# RelayWingTester.net
KiCad netlist of a schematic drawn in EAGLE
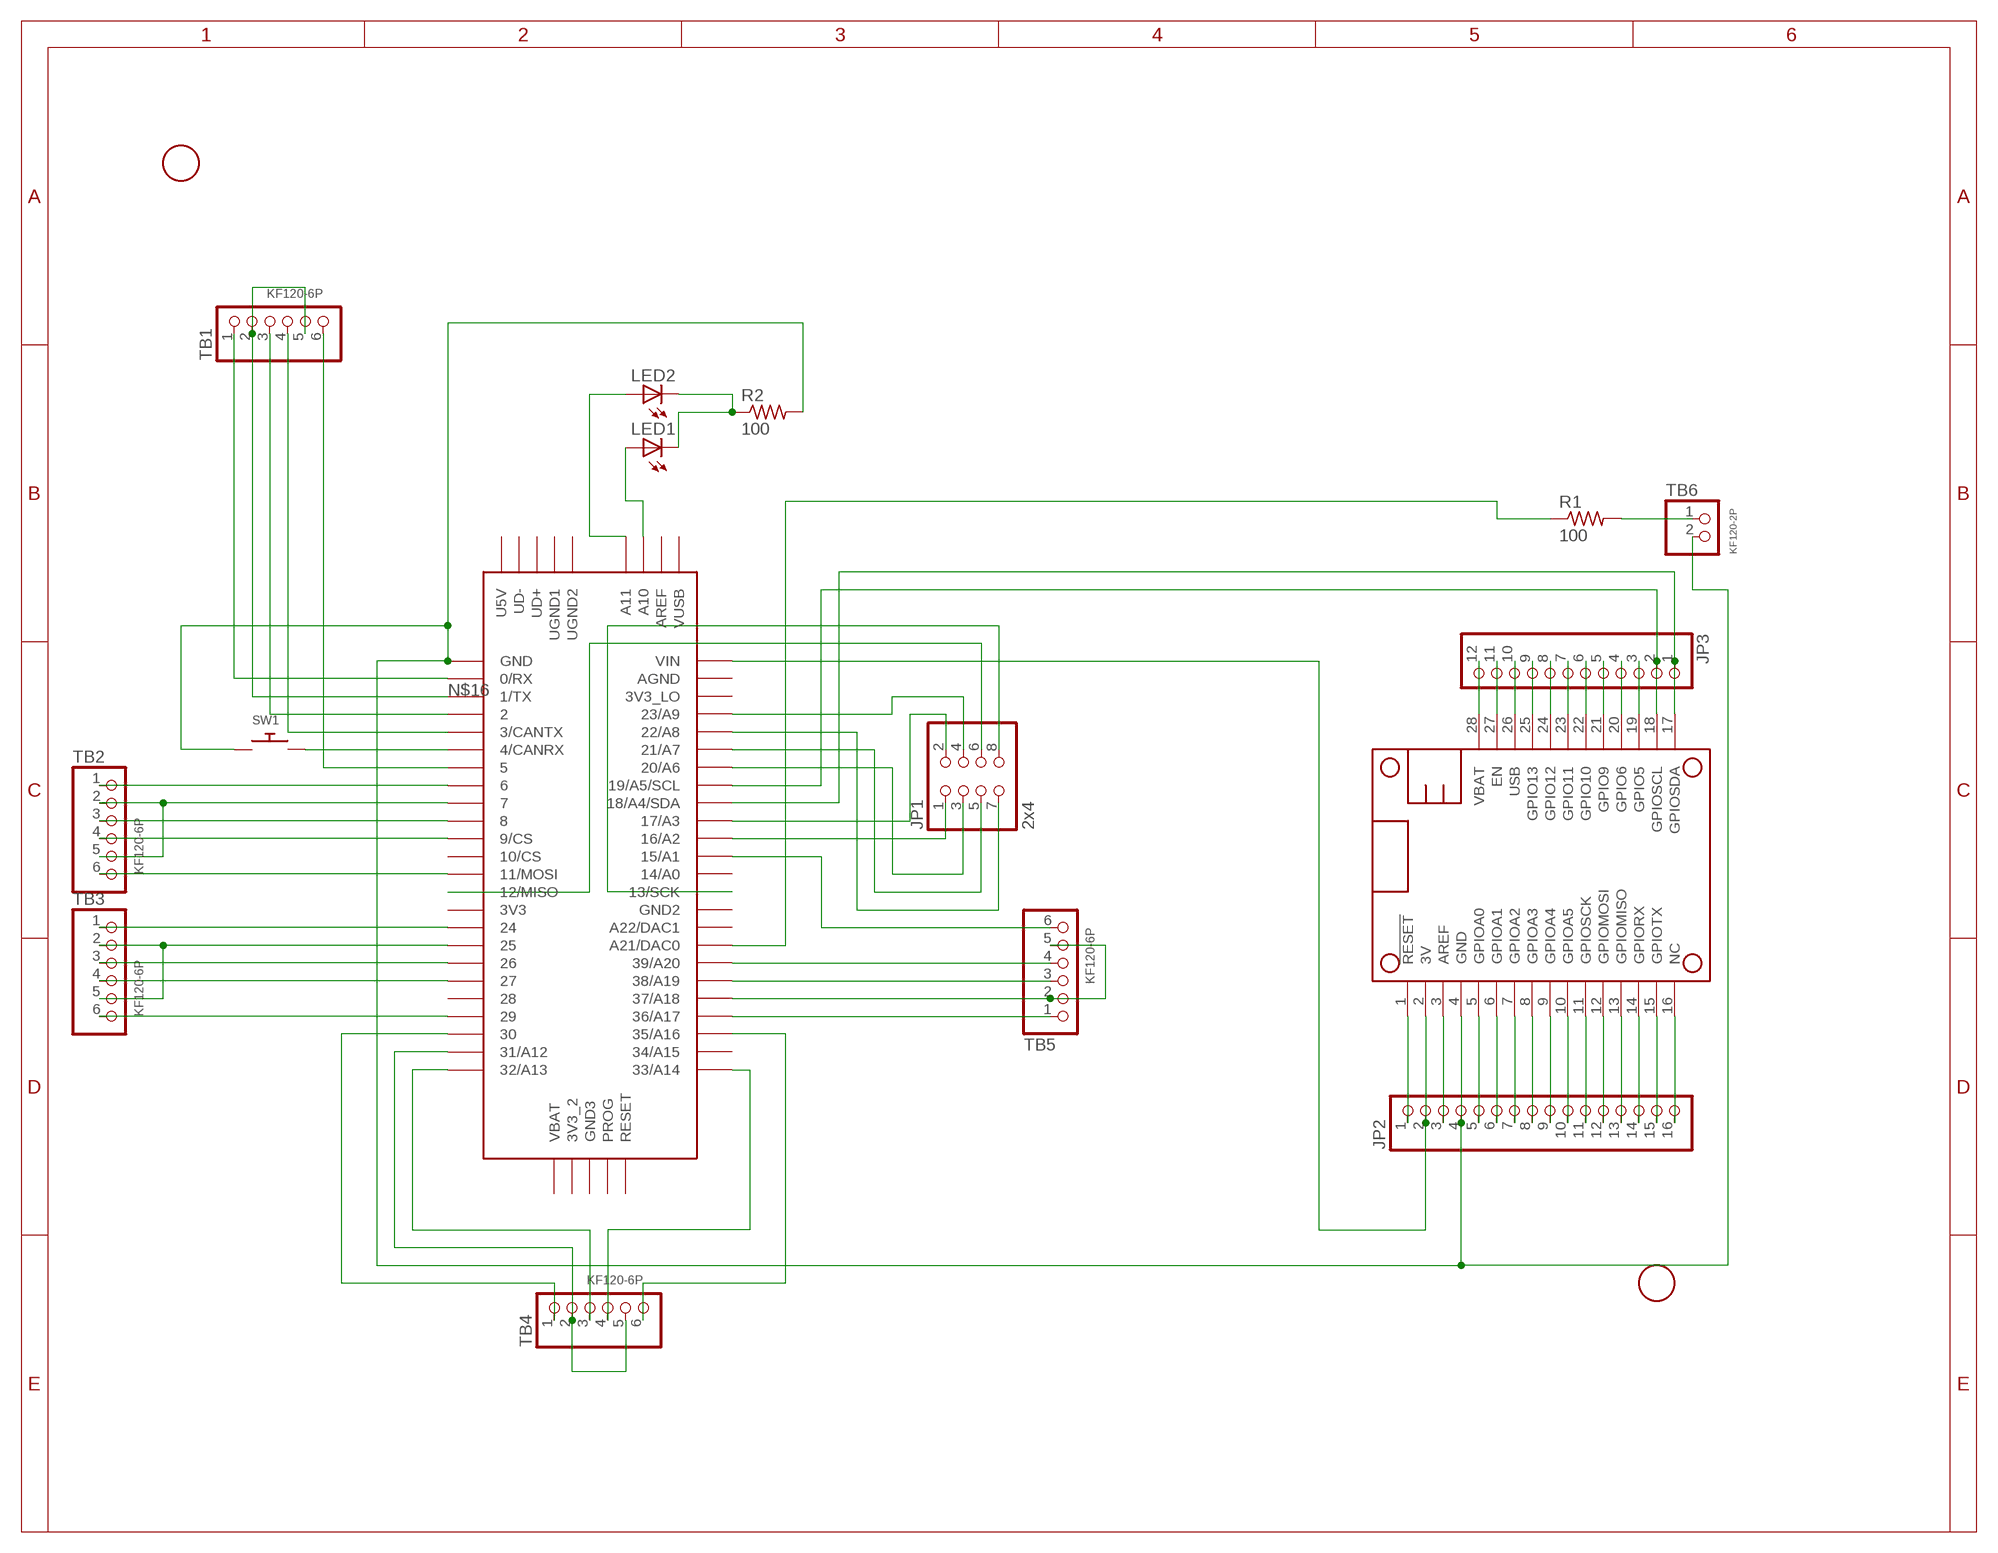
[diagram p0: schematic, sheet 1]

(export (version "E")
  (design (tool "Eeschema 10.0.6"))
  (components
    (comp (ref "JP1")
      (value "2x4")
      (footprint "eagle-import:2X04")
      (libsource (lib "eagle-import") (part "PINHD-2X4"))
    )
    (comp (ref "JP2")
      (value "PINHD-1X16")
      (footprint "eagle-import:1X16")
      (libsource (lib "eagle-import") (part "PINHD-1X16"))
    )
    (comp (ref "JP3")
      (value "PINHD-1X12")
      (footprint "eagle-import:1X12")
      (libsource (lib "eagle-import") (part "PINHD-1X12"))
    )
    (comp (ref "LED1")
      (value "LED5MM")
      (footprint "eagle-import:LED5MM")
      (libsource (lib "eagle-import") (part "LED5MM"))
    )
    (comp (ref "LED2")
      (value "LED5MM")
      (footprint "eagle-import:LED5MM")
      (libsource (lib "eagle-import") (part "LED5MM"))
    )
    (comp (ref "MS1")
      (value "FEATHERWING_NODIM")
      (footprint "eagle-import:FEATHERWING_DIM")
      (libsource (lib "eagle-import") (part "FEATHERWING_NODIM"))
    )
    (comp (ref "R1")
      (value "100")
      (footprint "eagle-import:0207_10")
      (libsource (lib "eagle-import") (part "resistor_348_R-US_0207/10"))
    )
    (comp (ref "R2")
      (value "100")
      (footprint "eagle-import:0207_10")
      (libsource (lib "eagle-import") (part "R-US_0207/10"))
    )
    (comp (ref "SW1")
      (value "SWITCH_PUSHBUTTONSOFTTOUCHSMD_SJ")
      (footprint "eagle-import:PUSHBUTTON_SMD_SJ")
      (libsource (lib "eagle-import") (part "SWITCH_PUSHBUTTONSOFTTOUCHSMD_SJ"))
    )
    (comp (ref "TB1")
      (value "KF120-6P")
      (footprint "eagle-import:KF120-6P_ROUND")
      (libsource (lib "eagle-import") (part "KF120-6P"))
    )
    (comp (ref "TB2")
      (value "KF120-6P")
      (footprint "eagle-import:KF120-6P_ROUND")
      (libsource (lib "eagle-import") (part "KF120-6P"))
    )
    (comp (ref "TB3")
      (value "KF120-6P")
      (footprint "eagle-import:KF120-6P_ROUND")
      (libsource (lib "eagle-import") (part "KF120-6P"))
    )
    (comp (ref "TB4")
      (value "KF120-6P")
      (footprint "eagle-import:KF120-6P_ROUND")
      (libsource (lib "eagle-import") (part "KF120-6P"))
    )
    (comp (ref "TB5")
      (value "KF120-6P")
      (footprint "eagle-import:KF120-6P_ROUND")
      (libsource (lib "eagle-import") (part "KF120-6P"))
    )
    (comp (ref "TB6")
      (value "KF120-2P")
      (footprint "eagle-import:KF120-2P_ROUND")
      (libsource (lib "eagle-import") (part "KF120-2P"))
    )
    (comp (ref "U$2")
      (value "FIDUCIAL")
      (footprint "eagle-import:FIDUCIAL_1MM")
      (libsource (lib "eagle-import") (part "FIDUCIAL"))
    )
    (comp (ref "U$3")
      (value "FIDUCIAL")
      (footprint "eagle-import:FIDUCIAL_1MM")
      (libsource (lib "eagle-import") (part "FIDUCIAL"))
    )
    (comp (ref "U$4")
      (value "TEENSY_3.5/3.6")
      (footprint "eagle-import:TEENSY_3.5_3.6")
      (libsource (lib "eagle-import") (part "TEENSY_3.5/3.6"))
    )
  )
  (nets
    (net (code "1") (name "/N$16") (class "Default")
      (node (ref "TB1") (pin "1") (pinfunction "1_1") (pintype "passive"))
      (node (ref "U$4") (pin "0/RX") (pinfunction "0/RX_0/RX") (pintype "bidirectional"))
    )
    (net (code "2") (name "Net-(JP1-Pad1)") (class "Default")
      (node (ref "JP1") (pin "1") (pinfunction "1_1") (pintype "passive"))
      (node (ref "U$4") (pin "16/A2") (pinfunction "16/A2_16/A2") (pintype "bidirectional"))
    )
    (net (code "3") (name "Net-(JP1-Pad2)") (class "Default")
      (node (ref "JP1") (pin "2") (pinfunction "2_2") (pintype "passive"))
      (node (ref "U$4") (pin "17/A3") (pinfunction "17/A3_17/A3") (pintype "bidirectional"))
    )
    (net (code "4") (name "Net-(JP1-Pad3)") (class "Default")
      (node (ref "JP1") (pin "3") (pinfunction "3_3") (pintype "passive"))
      (node (ref "U$4") (pin "20/A6") (pinfunction "20/A6_20/A6") (pintype "bidirectional"))
    )
    (net (code "5") (name "Net-(JP1-Pad4)") (class "Default")
      (node (ref "JP1") (pin "4") (pinfunction "4_4") (pintype "passive"))
      (node (ref "U$4") (pin "23/A9") (pinfunction "23/A9_23/A9") (pintype "bidirectional"))
    )
    (net (code "6") (name "Net-(JP1-Pad5)") (class "Default")
      (node (ref "JP1") (pin "5") (pinfunction "5_5") (pintype "passive"))
      (node (ref "U$4") (pin "21/A7") (pinfunction "21/A7_21/A7") (pintype "bidirectional"))
    )
    (net (code "7") (name "Net-(JP1-Pad6)") (class "Default")
      (node (ref "JP1") (pin "6") (pinfunction "6_6") (pintype "passive"))
      (node (ref "U$4") (pin "12/MISO") (pinfunction "12/MISO_12/MISO") (pintype "bidirectional"))
    )
    (net (code "8") (name "Net-(JP1-Pad7)") (class "Default")
      (node (ref "JP1") (pin "7") (pinfunction "7_7") (pintype "passive"))
      (node (ref "U$4") (pin "22/A8") (pinfunction "22/A8_22/A8") (pintype "bidirectional"))
    )
    (net (code "9") (name "Net-(JP1-Pad8)") (class "Default")
      (node (ref "JP1") (pin "8") (pinfunction "8_8") (pintype "passive"))
      (node (ref "U$4") (pin "13/SCK") (pinfunction "13/SCK_13/SCK") (pintype "bidirectional"))
    )
    (net (code "10") (name "Net-(LED1-C)") (class "Default")
      (node (ref "LED1") (pin "K") (pinfunction "C_K") (pintype "passive"))
      (node (ref "LED2") (pin "K") (pinfunction "C_K") (pintype "passive"))
      (node (ref "R2") (pin "1") (pinfunction "1_1") (pintype "passive"))
    )
    (net (code "11") (name "Net-(LED1-PadA)") (class "Default")
      (node (ref "LED1") (pin "A") (pinfunction "A_A") (pintype "passive"))
      (node (ref "U$4") (pin "A10") (pinfunction "A10_A10") (pintype "bidirectional"))
    )
    (net (code "12") (name "Net-(LED2-PadA)") (class "Default")
      (node (ref "LED2") (pin "A") (pinfunction "A_A") (pintype "passive"))
      (node (ref "U$4") (pin "A11") (pinfunction "A11_A11") (pintype "bidirectional"))
    )
    (net (code "13") (name "Net-(MS1-3V)") (class "Default")
      (node (ref "JP2") (pin "2") (pinfunction "2_2") (pintype "passive"))
      (node (ref "MS1") (pin "2") (pinfunction "3V_2") (pintype "power_in"))
      (node (ref "U$4") (pin "VIN") (pinfunction "VIN_VIN") (pintype "bidirectional"))
    )
    (net (code "14") (name "Net-(MS1-AREF)") (class "Default")
      (node (ref "JP2") (pin "3") (pinfunction "3_3") (pintype "passive"))
      (node (ref "MS1") (pin "3") (pinfunction "AREF_3") (pintype "passive"))
    )
    (net (code "15") (name "Net-(MS1-EN)") (class "Default")
      (node (ref "JP3") (pin "11") (pinfunction "11_11") (pintype "passive"))
      (node (ref "MS1") (pin "27") (pinfunction "EN_27") (pintype "passive"))
    )
    (net (code "16") (name "Net-(MS1-GND)") (class "Default")
      (node (ref "JP2") (pin "4") (pinfunction "4_4") (pintype "passive"))
      (node (ref "MS1") (pin "4") (pinfunction "GND_4") (pintype "power_in"))
      (node (ref "R2") (pin "2") (pinfunction "2_2") (pintype "passive"))
      (node (ref "SW1") (pin "P$1") (pinfunction "P$1_P$1") (pintype "passive"))
      (node (ref "TB6") (pin "2") (pinfunction "2_2") (pintype "passive"))
      (node (ref "U$4") (pin "GND") (pinfunction "GND_GND") (pintype "bidirectional"))
    )
    (net (code "17") (name "Net-(MS1-GPIO5)") (class "Default")
      (node (ref "JP3") (pin "3") (pinfunction "3_3") (pintype "passive"))
      (node (ref "MS1") (pin "19") (pinfunction "GPIO5_19") (pintype "bidirectional"))
    )
    (net (code "18") (name "Net-(MS1-GPIO6)") (class "Default")
      (node (ref "JP3") (pin "4") (pinfunction "4_4") (pintype "passive"))
      (node (ref "MS1") (pin "20") (pinfunction "GPIO6_20") (pintype "bidirectional"))
    )
    (net (code "19") (name "Net-(MS1-GPIO9)") (class "Default")
      (node (ref "JP3") (pin "5") (pinfunction "5_5") (pintype "passive"))
      (node (ref "MS1") (pin "21") (pinfunction "GPIO9_21") (pintype "bidirectional"))
    )
    (net (code "20") (name "Net-(MS1-GPIO10)") (class "Default")
      (node (ref "JP3") (pin "6") (pinfunction "6_6") (pintype "passive"))
      (node (ref "MS1") (pin "22") (pinfunction "GPIO10_22") (pintype "bidirectional"))
    )
    (net (code "21") (name "Net-(MS1-GPIO11)") (class "Default")
      (node (ref "JP3") (pin "7") (pinfunction "7_7") (pintype "passive"))
      (node (ref "MS1") (pin "23") (pinfunction "GPIO11_23") (pintype "bidirectional"))
    )
    (net (code "22") (name "Net-(MS1-GPIO12)") (class "Default")
      (node (ref "JP3") (pin "8") (pinfunction "8_8") (pintype "passive"))
      (node (ref "MS1") (pin "24") (pinfunction "GPIO12_24") (pintype "bidirectional"))
    )
    (net (code "23") (name "Net-(MS1-GPIO13)") (class "Default")
      (node (ref "JP3") (pin "9") (pinfunction "9_9") (pintype "passive"))
      (node (ref "MS1") (pin "25") (pinfunction "GPIO13_25") (pintype "bidirectional"))
    )
    (net (code "24") (name "Net-(MS1-GPIOA0)") (class "Default")
      (node (ref "JP2") (pin "5") (pinfunction "5_5") (pintype "passive"))
      (node (ref "MS1") (pin "5") (pinfunction "GPIOA0_5") (pintype "bidirectional"))
    )
    (net (code "25") (name "Net-(MS1-GPIOA1)") (class "Default")
      (node (ref "JP2") (pin "6") (pinfunction "6_6") (pintype "passive"))
      (node (ref "MS1") (pin "6") (pinfunction "GPIOA1_6") (pintype "bidirectional"))
    )
    (net (code "26") (name "Net-(MS1-GPIOA2)") (class "Default")
      (node (ref "JP2") (pin "7") (pinfunction "7_7") (pintype "passive"))
      (node (ref "MS1") (pin "7") (pinfunction "GPIOA2_7") (pintype "bidirectional"))
    )
    (net (code "27") (name "Net-(MS1-GPIOA3)") (class "Default")
      (node (ref "JP2") (pin "8") (pinfunction "8_8") (pintype "passive"))
      (node (ref "MS1") (pin "8") (pinfunction "GPIOA3_8") (pintype "bidirectional"))
    )
    (net (code "28") (name "Net-(MS1-GPIOA4)") (class "Default")
      (node (ref "JP2") (pin "9") (pinfunction "9_9") (pintype "passive"))
      (node (ref "MS1") (pin "9") (pinfunction "GPIOA4_9") (pintype "bidirectional"))
    )
    (net (code "29") (name "Net-(MS1-GPIOA5)") (class "Default")
      (node (ref "JP2") (pin "10") (pinfunction "10_10") (pintype "passive"))
      (node (ref "MS1") (pin "10") (pinfunction "GPIOA5_10") (pintype "bidirectional"))
    )
    (net (code "30") (name "Net-(MS1-GPIOMISO)") (class "Default")
      (node (ref "JP2") (pin "13") (pinfunction "13_13") (pintype "passive"))
      (node (ref "MS1") (pin "13") (pinfunction "GPIOMISO_13") (pintype "bidirectional"))
    )
    (net (code "31") (name "Net-(MS1-GPIOMOSI)") (class "Default")
      (node (ref "JP2") (pin "12") (pinfunction "12_12") (pintype "passive"))
      (node (ref "MS1") (pin "12") (pinfunction "GPIOMOSI_12") (pintype "bidirectional"))
    )
    (net (code "32") (name "Net-(MS1-GPIORX)") (class "Default")
      (node (ref "JP2") (pin "14") (pinfunction "14_14") (pintype "passive"))
      (node (ref "MS1") (pin "14") (pinfunction "GPIORX_14") (pintype "bidirectional"))
    )
    (net (code "33") (name "Net-(MS1-GPIOSCK)") (class "Default")
      (node (ref "JP2") (pin "11") (pinfunction "11_11") (pintype "passive"))
      (node (ref "MS1") (pin "11") (pinfunction "GPIOSCK_11") (pintype "bidirectional"))
    )
    (net (code "34") (name "Net-(MS1-GPIOSCL)") (class "Default")
      (node (ref "JP3") (pin "2") (pinfunction "2_2") (pintype "passive"))
      (node (ref "MS1") (pin "18") (pinfunction "GPIOSCL_18") (pintype "bidirectional"))
      (node (ref "U$4") (pin "19/A5/SCL") (pinfunction "19/A5/SCL_19/A5/SCL") (pintype "bidirectional"))
    )
    (net (code "35") (name "Net-(MS1-GPIOSDA)") (class "Default")
      (node (ref "JP3") (pin "1") (pinfunction "1_1") (pintype "passive"))
      (node (ref "MS1") (pin "17") (pinfunction "GPIOSDA_17") (pintype "bidirectional"))
      (node (ref "U$4") (pin "18/A4/SDA") (pinfunction "18/A4/SDA_18/A4/SDA") (pintype "bidirectional"))
    )
    (net (code "36") (name "Net-(MS1-GPIOTX)") (class "Default")
      (node (ref "JP2") (pin "15") (pinfunction "15_15") (pintype "passive"))
      (node (ref "MS1") (pin "15") (pinfunction "GPIOTX_15") (pintype "bidirectional"))
    )
    (net (code "37") (name "Net-(MS1-NC)") (class "Default")
      (node (ref "JP2") (pin "16") (pinfunction "16_16") (pintype "passive"))
      (node (ref "MS1") (pin "16") (pinfunction "NC_16") (pintype "passive"))
    )
    (net (code "38") (name "Net-(MS1-USB)") (class "Default")
      (node (ref "JP3") (pin "10") (pinfunction "10_10") (pintype "passive"))
      (node (ref "MS1") (pin "26") (pinfunction "USB_26") (pintype "power_in"))
    )
    (net (code "39") (name "Net-(MS1-VBAT)") (class "Default")
      (node (ref "JP3") (pin "12") (pinfunction "12_12") (pintype "passive"))
      (node (ref "MS1") (pin "28") (pinfunction "VBAT_28") (pintype "power_in"))
    )
    (net (code "40") (name "Net-(MS1-~{RESET})") (class "Default")
      (node (ref "JP2") (pin "1") (pinfunction "1_1") (pintype "passive"))
      (node (ref "MS1") (pin "1") (pinfunction "~{RESET}_1") (pintype "input"))
    )
    (net (code "41") (name "Net-(R1-Pad2)") (class "Default")
      (node (ref "R1") (pin "2") (pinfunction "2_2") (pintype "passive"))
      (node (ref "TB6") (pin "1") (pinfunction "1_1") (pintype "passive"))
    )
    (net (code "42") (name "Net-(SW1-PadP$2)") (class "Default")
      (node (ref "SW1") (pin "P$2") (pinfunction "P$2_P$2") (pintype "passive"))
      (node (ref "U$4") (pin "4/CANRX") (pinfunction "4/CANRX_4/CANRX") (pintype "bidirectional"))
    )
    (net (code "43") (name "Net-(TB1-Pad2)") (class "Default")
      (node (ref "TB1") (pin "2") (pinfunction "2_2") (pintype "passive"))
      (node (ref "TB1") (pin "5") (pinfunction "5_5") (pintype "passive"))
      (node (ref "U$4") (pin "1/TX") (pinfunction "1/TX_1/TX") (pintype "bidirectional"))
    )
    (net (code "44") (name "Net-(TB1-Pad3)") (class "Default")
      (node (ref "TB1") (pin "3") (pinfunction "3_3") (pintype "passive"))
      (node (ref "U$4") (pin "2") (pinfunction "2_2") (pintype "bidirectional"))
    )
    (net (code "45") (name "Net-(TB1-Pad4)") (class "Default")
      (node (ref "TB1") (pin "4") (pinfunction "4_4") (pintype "passive"))
      (node (ref "U$4") (pin "3/CANTX") (pinfunction "3/CANTX_3/CANTX") (pintype "bidirectional"))
    )
    (net (code "46") (name "Net-(TB1-Pad6)") (class "Default")
      (node (ref "TB1") (pin "6") (pinfunction "6_6") (pintype "passive"))
      (node (ref "U$4") (pin "5") (pinfunction "5_5") (pintype "bidirectional"))
    )
    (net (code "47") (name "Net-(TB2-Pad1)") (class "Default")
      (node (ref "TB2") (pin "1") (pinfunction "1_1") (pintype "passive"))
      (node (ref "U$4") (pin "6") (pinfunction "6_6") (pintype "bidirectional"))
    )
    (net (code "48") (name "Net-(TB2-Pad2)") (class "Default")
      (node (ref "TB2") (pin "2") (pinfunction "2_2") (pintype "passive"))
      (node (ref "TB2") (pin "5") (pinfunction "5_5") (pintype "passive"))
      (node (ref "U$4") (pin "7") (pinfunction "7_7") (pintype "bidirectional"))
    )
    (net (code "49") (name "Net-(TB2-Pad3)") (class "Default")
      (node (ref "TB2") (pin "3") (pinfunction "3_3") (pintype "passive"))
      (node (ref "U$4") (pin "8") (pinfunction "8_8") (pintype "bidirectional"))
    )
    (net (code "50") (name "Net-(TB2-Pad4)") (class "Default")
      (node (ref "TB2") (pin "4") (pinfunction "4_4") (pintype "passive"))
      (node (ref "U$4") (pin "9/CS") (pinfunction "9/CS_9/CS") (pintype "bidirectional"))
    )
    (net (code "51") (name "Net-(TB2-Pad6)") (class "Default")
      (node (ref "TB2") (pin "6") (pinfunction "6_6") (pintype "passive"))
      (node (ref "U$4") (pin "11/MOSI") (pinfunction "11/MOSI_11/MOSI") (pintype "bidirectional"))
    )
    (net (code "52") (name "Net-(TB3-Pad1)") (class "Default")
      (node (ref "TB3") (pin "1") (pinfunction "1_1") (pintype "passive"))
      (node (ref "U$4") (pin "24") (pinfunction "24_24") (pintype "bidirectional"))
    )
    (net (code "53") (name "Net-(TB3-Pad2)") (class "Default")
      (node (ref "TB3") (pin "2") (pinfunction "2_2") (pintype "passive"))
      (node (ref "TB3") (pin "5") (pinfunction "5_5") (pintype "passive"))
      (node (ref "U$4") (pin "25") (pinfunction "25_25") (pintype "bidirectional"))
    )
    (net (code "54") (name "Net-(TB3-Pad3)") (class "Default")
      (node (ref "TB3") (pin "3") (pinfunction "3_3") (pintype "passive"))
      (node (ref "U$4") (pin "26") (pinfunction "26_26") (pintype "bidirectional"))
    )
    (net (code "55") (name "Net-(TB3-Pad4)") (class "Default")
      (node (ref "TB3") (pin "4") (pinfunction "4_4") (pintype "passive"))
      (node (ref "U$4") (pin "27") (pinfunction "27_27") (pintype "bidirectional"))
    )
    (net (code "56") (name "Net-(TB3-Pad6)") (class "Default")
      (node (ref "TB3") (pin "6") (pinfunction "6_6") (pintype "passive"))
      (node (ref "U$4") (pin "29") (pinfunction "29_29") (pintype "bidirectional"))
    )
    (net (code "57") (name "Net-(TB4-Pad1)") (class "Default")
      (node (ref "TB4") (pin "1") (pinfunction "1_1") (pintype "passive"))
      (node (ref "U$4") (pin "30") (pinfunction "30_30") (pintype "bidirectional"))
    )
    (net (code "58") (name "Net-(TB4-Pad2)") (class "Default")
      (node (ref "TB4") (pin "2") (pinfunction "2_2") (pintype "passive"))
      (node (ref "TB4") (pin "5") (pinfunction "5_5") (pintype "passive"))
      (node (ref "U$4") (pin "31/A12") (pinfunction "31/A12_31/A12") (pintype "bidirectional"))
    )
    (net (code "59") (name "Net-(TB4-Pad3)") (class "Default")
      (node (ref "TB4") (pin "3") (pinfunction "3_3") (pintype "passive"))
      (node (ref "U$4") (pin "32/A13") (pinfunction "32/A13_32/A13") (pintype "bidirectional"))
    )
    (net (code "60") (name "Net-(TB4-Pad4)") (class "Default")
      (node (ref "TB4") (pin "4") (pinfunction "4_4") (pintype "passive"))
      (node (ref "U$4") (pin "33/A14") (pinfunction "33/A14_33/A14") (pintype "bidirectional"))
    )
    (net (code "61") (name "Net-(TB4-Pad6)") (class "Default")
      (node (ref "TB4") (pin "6") (pinfunction "6_6") (pintype "passive"))
      (node (ref "U$4") (pin "35/A16") (pinfunction "35/A16_35/A16") (pintype "bidirectional"))
    )
    (net (code "62") (name "Net-(TB5-Pad1)") (class "Default")
      (node (ref "TB5") (pin "1") (pinfunction "1_1") (pintype "passive"))
      (node (ref "U$4") (pin "36/A17") (pinfunction "36/A17_36/A17") (pintype "bidirectional"))
    )
    (net (code "63") (name "Net-(TB5-Pad2)") (class "Default")
      (node (ref "TB5") (pin "2") (pinfunction "2_2") (pintype "passive"))
      (node (ref "TB5") (pin "5") (pinfunction "5_5") (pintype "passive"))
      (node (ref "U$4") (pin "37/A18") (pinfunction "37/A18_37/A18") (pintype "bidirectional"))
    )
    (net (code "64") (name "Net-(TB5-Pad3)") (class "Default")
      (node (ref "TB5") (pin "3") (pinfunction "3_3") (pintype "passive"))
      (node (ref "U$4") (pin "38/A19") (pinfunction "38/A19_38/A19") (pintype "bidirectional"))
    )
    (net (code "65") (name "Net-(TB5-Pad4)") (class "Default")
      (node (ref "TB5") (pin "4") (pinfunction "4_4") (pintype "passive"))
      (node (ref "U$4") (pin "39/A20") (pinfunction "39/A20_39/A20") (pintype "bidirectional"))
    )
    (net (code "66") (name "Net-(TB5-Pad6)") (class "Default")
      (node (ref "TB5") (pin "6") (pinfunction "6_6") (pintype "passive"))
      (node (ref "U$4") (pin "15/A1") (pinfunction "15/A1_15/A1") (pintype "bidirectional"))
    )
    (net (code "67") (name "Net-(U$4-A21{slash}DAC0)") (class "Default")
      (node (ref "R1") (pin "1") (pinfunction "1_1") (pintype "passive"))
      (node (ref "U$4") (pin "21/DAC0") (pinfunction "A21/DAC0_21/DAC0") (pintype "bidirectional"))
    )
    (net (code "68") (name "unconnected-(U$4-Pad3V3)") (class "Default")
      (node (ref "U$4") (pin "3V3") (pinfunction "3V3_3V3") (pintype "bidirectional"))
    )
    (net (code "69") (name "unconnected-(U$4-Pad3V3_2)") (class "Default")
      (node (ref "U$4") (pin "3V3_2") (pinfunction "3V3_2_3V3_2") (pintype "bidirectional"))
    )
    (net (code "70") (name "unconnected-(U$4-Pad3V3_LO)") (class "Default")
      (node (ref "U$4") (pin "3V3_LO") (pinfunction "3V3_LO_3V3_LO") (pintype "bidirectional"))
    )
    (net (code "71") (name "unconnected-(U$4-Pad10{slash}CS)") (class "Default")
      (node (ref "U$4") (pin "10/CS") (pinfunction "10/CS_10/CS") (pintype "bidirectional"))
    )
    (net (code "72") (name "unconnected-(U$4-Pad14{slash}A0)") (class "Default")
      (node (ref "U$4") (pin "14/A0") (pinfunction "14/A0_14/A0") (pintype "bidirectional"))
    )
    (net (code "73") (name "unconnected-(U$4-Pad28)") (class "Default")
      (node (ref "U$4") (pin "28") (pinfunction "28_28") (pintype "bidirectional"))
    )
    (net (code "74") (name "unconnected-(U$4-Pad34{slash}A15)") (class "Default")
      (node (ref "U$4") (pin "34/A15") (pinfunction "34/A15_34/A15") (pintype "bidirectional"))
    )
    (net (code "75") (name "unconnected-(U$4-PadA22{slash}DAC1)") (class "Default")
      (node (ref "U$4") (pin "A22/DAC1") (pinfunction "A22/DAC1_A22/DAC1") (pintype "bidirectional"))
    )
    (net (code "76") (name "unconnected-(U$4-PadAGND)") (class "Default")
      (node (ref "U$4") (pin "AGND") (pinfunction "AGND_AGND") (pintype "bidirectional"))
    )
    (net (code "77") (name "unconnected-(U$4-PadAREF)") (class "Default")
      (node (ref "U$4") (pin "AREF") (pinfunction "AREF_AREF") (pintype "bidirectional"))
    )
    (net (code "78") (name "unconnected-(U$4-PadGND2)") (class "Default")
      (node (ref "U$4") (pin "GND2") (pinfunction "GND2_GND2") (pintype "bidirectional"))
    )
    (net (code "79") (name "unconnected-(U$4-PadGND3)") (class "Default")
      (node (ref "U$4") (pin "GND3") (pinfunction "GND3_GND3") (pintype "bidirectional"))
    )
    (net (code "80") (name "unconnected-(U$4-PadPROG)") (class "Default")
      (node (ref "U$4") (pin "PROG") (pinfunction "PROG_PROG") (pintype "bidirectional"))
    )
    (net (code "81") (name "unconnected-(U$4-PadRESET)") (class "Default")
      (node (ref "U$4") (pin "RESET") (pinfunction "RESET_RESET") (pintype "bidirectional"))
    )
    (net (code "82") (name "unconnected-(U$4-PadU5V)") (class "Default")
      (node (ref "U$4") (pin "U5V") (pinfunction "U5V_U5V") (pintype "bidirectional"))
    )
    (net (code "83") (name "unconnected-(U$4-PadUD+)") (class "Default")
      (node (ref "U$4") (pin "UD+") (pinfunction "UD+_UD+") (pintype "bidirectional"))
    )
    (net (code "84") (name "unconnected-(U$4-PadUD-)") (class "Default")
      (node (ref "U$4") (pin "UD-") (pinfunction "UD-_UD-") (pintype "bidirectional"))
    )
    (net (code "85") (name "unconnected-(U$4-PadUGND1)") (class "Default")
      (node (ref "U$4") (pin "UGND1") (pinfunction "UGND1_UGND1") (pintype "bidirectional"))
    )
    (net (code "86") (name "unconnected-(U$4-PadUGND2)") (class "Default")
      (node (ref "U$4") (pin "UGND2") (pinfunction "UGND2_UGND2") (pintype "bidirectional"))
    )
    (net (code "87") (name "unconnected-(U$4-PadVBAT)") (class "Default")
      (node (ref "U$4") (pin "VBAT") (pinfunction "VBAT_VBAT") (pintype "bidirectional"))
    )
    (net (code "88") (name "unconnected-(U$4-PadVUSB)") (class "Default")
      (node (ref "U$4") (pin "VUSB") (pinfunction "VUSB_VUSB") (pintype "bidirectional"))
    )
  )
)
